# High-Side_Driver.net
KiCad netlist of a schematic drawn in Altium Designer
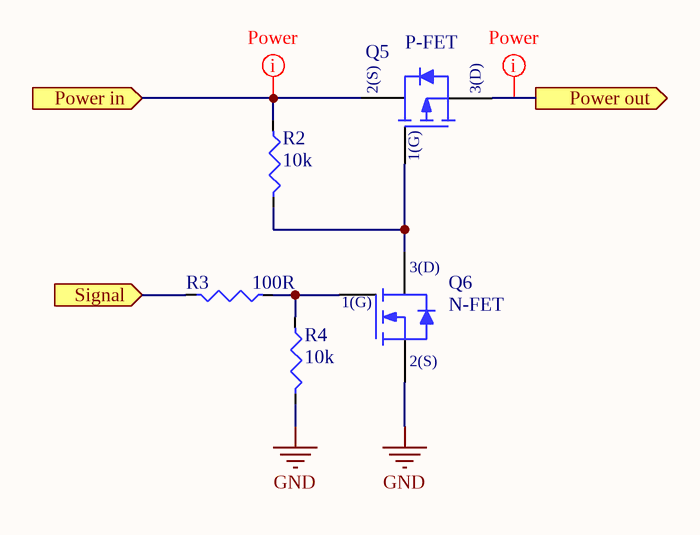
[diagram p0: High-Side Driver.SchDoc]

(export (version "E")
  (design (tool "Eeschema 10.0.6"))
  (components
    (comp (ref "Q5")
      (value "P-FET")
      (footprint "SOT23 - 3 pin")
      (description "P Channel MOSFET")
      (fields
        (field (name "MANUFACTURER") "Diodes Incorporated")
        (field (name "MANUFACTURER PART NUMBER") "DMP3130L-7")
      )
      (libsource (lib "Integrated Component Library") (part "P Channel MOSFET 3.5A"))
    )
    (comp (ref "Q6")
      (value "N-FET")
      (footprint "SOT23 - 3 pin")
      (description "N Channel MOSFET")
      (fields
        (field (name "MANUFACTURER") "NXP Semiconductors")
        (field (name "MANUFACTURER PART NUMBER") "2N7002,215")
      )
      (libsource (lib "Integrated Component Library") (part "N Channel MOSFET"))
    )
    (comp (ref "R2")
      (value "~")
      (footprint "Resistor - 1206")
      (description "Resistor")
      (fields
        (field (name "MANUFACTURER") "Vishay Dale")
        (field (name "TOLERANCE") "±1%")
        (field (name "RESISTANCE (OHMS)") "10k")
      )
      (libsource (lib "Integrated Component Library") (part "10k 1206 1%"))
    )
    (comp (ref "R3")
      (value "2k 1206 5%")
      (footprint "Resistor - 1206")
      (description "Resistor")
      (fields
        (field (name "MANUFACTURER") "Yageo")
        (field (name "MANUFACTURER PART NUMBER") "RC1206FR-07100RL")
        (field (name "RESISTANCE (OHMS)") "100R")
      )
      (libsource (lib "Integrated Component Library") (part "2k 1206 5%"))
    )
    (comp (ref "R4")
      (value "~")
      (footprint "Resistor - 1206")
      (description "Resistor")
      (fields
        (field (name "MANUFACTURER") "Vishay Dale")
        (field (name "TOLERANCE") "±1%")
        (field (name "RESISTANCE (OHMS)") "10k")
      )
      (libsource (lib "Integrated Component Library") (part "10k 1206 1%"))
    )
  )
  (nets
    (net (code "1") (name "/Power in") (class "Default")
      (node (ref "Q5") (pin "2") (pinfunction "Source_2") (pintype "passive"))
      (node (ref "R2") (pin "1") (pinfunction "1_1") (pintype "passive"))
    )
    (net (code "2") (name "/Power out") (class "Default")
      (node (ref "Q5") (pin "3") (pinfunction "Drain_3") (pintype "passive"))
    )
    (net (code "3") (name "/Signal") (class "Default")
      (node (ref "R3") (pin "1") (pinfunction "1_1") (pintype "passive"))
    )
    (net (code "4") (name "GND") (class "Default")
      (node (ref "Q6") (pin "2") (pinfunction "Source_2") (pintype "passive"))
      (node (ref "R4") (pin "2") (pinfunction "2_2") (pintype "passive"))
    )
    (net (code "5") (name "Net-(Q5-Gate)") (class "Default")
      (node (ref "Q5") (pin "1") (pinfunction "Gate_1") (pintype "passive"))
      (node (ref "Q6") (pin "3") (pinfunction "Drain_3") (pintype "passive"))
      (node (ref "R2") (pin "2") (pinfunction "2_2") (pintype "passive"))
    )
    (net (code "6") (name "Net-(Q6-Gate)") (class "Default")
      (node (ref "Q6") (pin "1") (pinfunction "Gate_1") (pintype "passive"))
      (node (ref "R3") (pin "2") (pinfunction "2_2") (pintype "passive"))
      (node (ref "R4") (pin "1") (pinfunction "1_1") (pintype "passive"))
    )
  )
)
